# Sheet1.net
KiCad netlist of a schematic drawn in Altium Designer
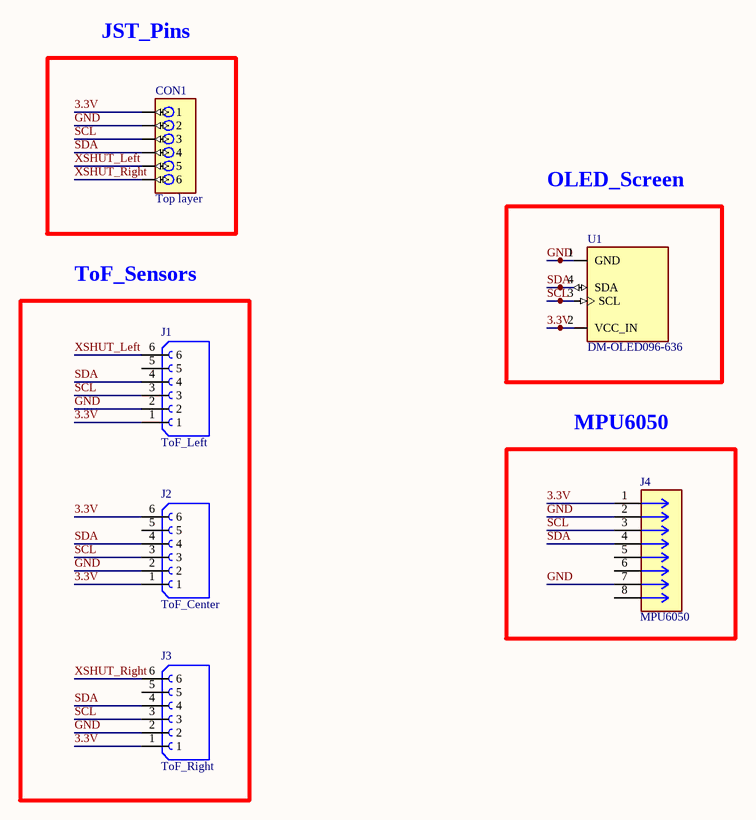
[diagram p0: Sheet1.SchDoc]

(export (version "E")
  (design (tool "Eeschema 10.0.6"))
  (components
    (comp (ref "CON1")
      (value "Top layer")
      (footprint "6 pin JST")
      (description "Connector Header Surface Mount 6 position 0.059 (1.50mm)")
      (fields (field (name "MF") "JST") (field (name "MP") "B6B-ZR"))
      (libsource (lib "Schlib1") (part "6 pin JST"))
    )
    (comp (ref "J1")
      (value "ToF_Left")
      (footprint "6 pin female header")
      (fields (field (name "MF") "Sullins Connector Solutions") (field (name "MP") "PPTC061LFBNRC"))
      (libsource (lib "Schlib2") (part "6 pin female header"))
    )
    (comp (ref "J2")
      (value "ToF_Center")
      (footprint "6 pin female header")
      (fields (field (name "MF") "Sullins Connector Solutions") (field (name "MP") "PPTC061LFBNRC"))
      (libsource (lib "Schlib2") (part "6 pin female header"))
    )
    (comp (ref "J3")
      (value "ToF_Right")
      (footprint "6 pin female header")
      (fields (field (name "MF") "Sullins Connector Solutions") (field (name "MP") "PPTC061LFBNRC"))
      (libsource (lib "Schlib2") (part "6 pin female header"))
    )
    (comp (ref "J4")
      (value "MPU6050")
      (footprint "8 Pin Female Headers")
      (fields (field (name "MP") "395011008"))
      (libsource (lib "Schlib1") (part "8 pin Female Headers"))
    )
    (comp (ref "U1")
      (value "DM-OLED096-636")
      (footprint "MODULE_DM-OLED096-636")
      (description "0.96â€ 128 X 64 MONOCHROME GRAPHIC OLED DISPLAY MODULE - I2C")
      (fields (field (name "MF") "Display Module"))
      (libsource (lib "Schlib2") (part "DM-OLED096-636"))
    )
  )
  (nets
    (net (code "1") (name "/3.3V") (class "Default")
      (node (ref "CON1") (pin "1") (pinfunction "1_1") (pintype "bidirectional"))
      (node (ref "J1") (pin "1") (pinfunction "1_1") (pintype "passive"))
      (node (ref "J2") (pin "1") (pinfunction "1_1") (pintype "passive"))
      (node (ref "J2") (pin "6") (pinfunction "6_6") (pintype "passive"))
      (node (ref "J3") (pin "1") (pinfunction "1_1") (pintype "passive"))
      (node (ref "J4") (pin "1") (pintype "passive"))
      (node (ref "U1") (pin "2") (pinfunction "VCC_IN_2") (pintype "power_in"))
    )
    (net (code "2") (name "/GND") (class "Default")
      (node (ref "CON1") (pin "2") (pinfunction "2_2") (pintype "bidirectional"))
      (node (ref "J1") (pin "2") (pinfunction "2_2") (pintype "passive"))
      (node (ref "J2") (pin "2") (pinfunction "2_2") (pintype "passive"))
      (node (ref "J3") (pin "2") (pinfunction "2_2") (pintype "passive"))
      (node (ref "J4") (pin "2") (pintype "passive"))
      (node (ref "J4") (pin "7") (pintype "passive"))
      (node (ref "U1") (pin "1") (pinfunction "GND_1") (pintype "power_in"))
    )
    (net (code "3") (name "/SCL") (class "Default")
      (node (ref "CON1") (pin "3") (pinfunction "3_3") (pintype "bidirectional"))
      (node (ref "J1") (pin "3") (pinfunction "3_3") (pintype "passive"))
      (node (ref "J2") (pin "3") (pinfunction "3_3") (pintype "passive"))
      (node (ref "J3") (pin "3") (pinfunction "3_3") (pintype "passive"))
      (node (ref "J4") (pin "3") (pintype "passive"))
      (node (ref "U1") (pin "3") (pinfunction "SCL_3") (pintype "input"))
    )
    (net (code "4") (name "/SDA") (class "Default")
      (node (ref "CON1") (pin "4") (pinfunction "4_4") (pintype "bidirectional"))
      (node (ref "J1") (pin "4") (pinfunction "4_4") (pintype "passive"))
      (node (ref "J2") (pin "4") (pinfunction "4_4") (pintype "passive"))
      (node (ref "J3") (pin "4") (pinfunction "4_4") (pintype "passive"))
      (node (ref "J4") (pin "4") (pintype "passive"))
      (node (ref "U1") (pin "4") (pinfunction "SDA_4") (pintype "bidirectional"))
    )
    (net (code "5") (name "/XSHUT_Left") (class "Default")
      (node (ref "CON1") (pin "5") (pinfunction "5_5") (pintype "bidirectional"))
      (node (ref "J1") (pin "6") (pinfunction "6_6") (pintype "passive"))
    )
    (net (code "6") (name "/XSHUT_Right") (class "Default")
      (node (ref "CON1") (pin "6") (pinfunction "6_6") (pintype "bidirectional"))
      (node (ref "J3") (pin "6") (pinfunction "6_6") (pintype "passive"))
    )
    (net (code "7") (name "unconnected-(J1-Pad5)") (class "Default")
      (node (ref "J1") (pin "5") (pinfunction "5_5") (pintype "passive"))
    )
    (net (code "8") (name "unconnected-(J2-Pad5)") (class "Default")
      (node (ref "J2") (pin "5") (pinfunction "5_5") (pintype "passive"))
    )
    (net (code "9") (name "unconnected-(J3-Pad5)") (class "Default")
      (node (ref "J3") (pin "5") (pinfunction "5_5") (pintype "passive"))
    )
    (net (code "10") (name "unconnected-(J4-Pad5)") (class "Default")
      (node (ref "J4") (pin "5") (pintype "passive"))
    )
    (net (code "11") (name "unconnected-(J4-Pad6)") (class "Default")
      (node (ref "J4") (pin "6") (pintype "passive"))
    )
    (net (code "12") (name "unconnected-(J4-Pad8)") (class "Default")
      (node (ref "J4") (pin "8") (pintype "passive"))
    )
  )
)
